# PWR_1_0.net
KiCad netlist of a schematic drawn in EAGLE
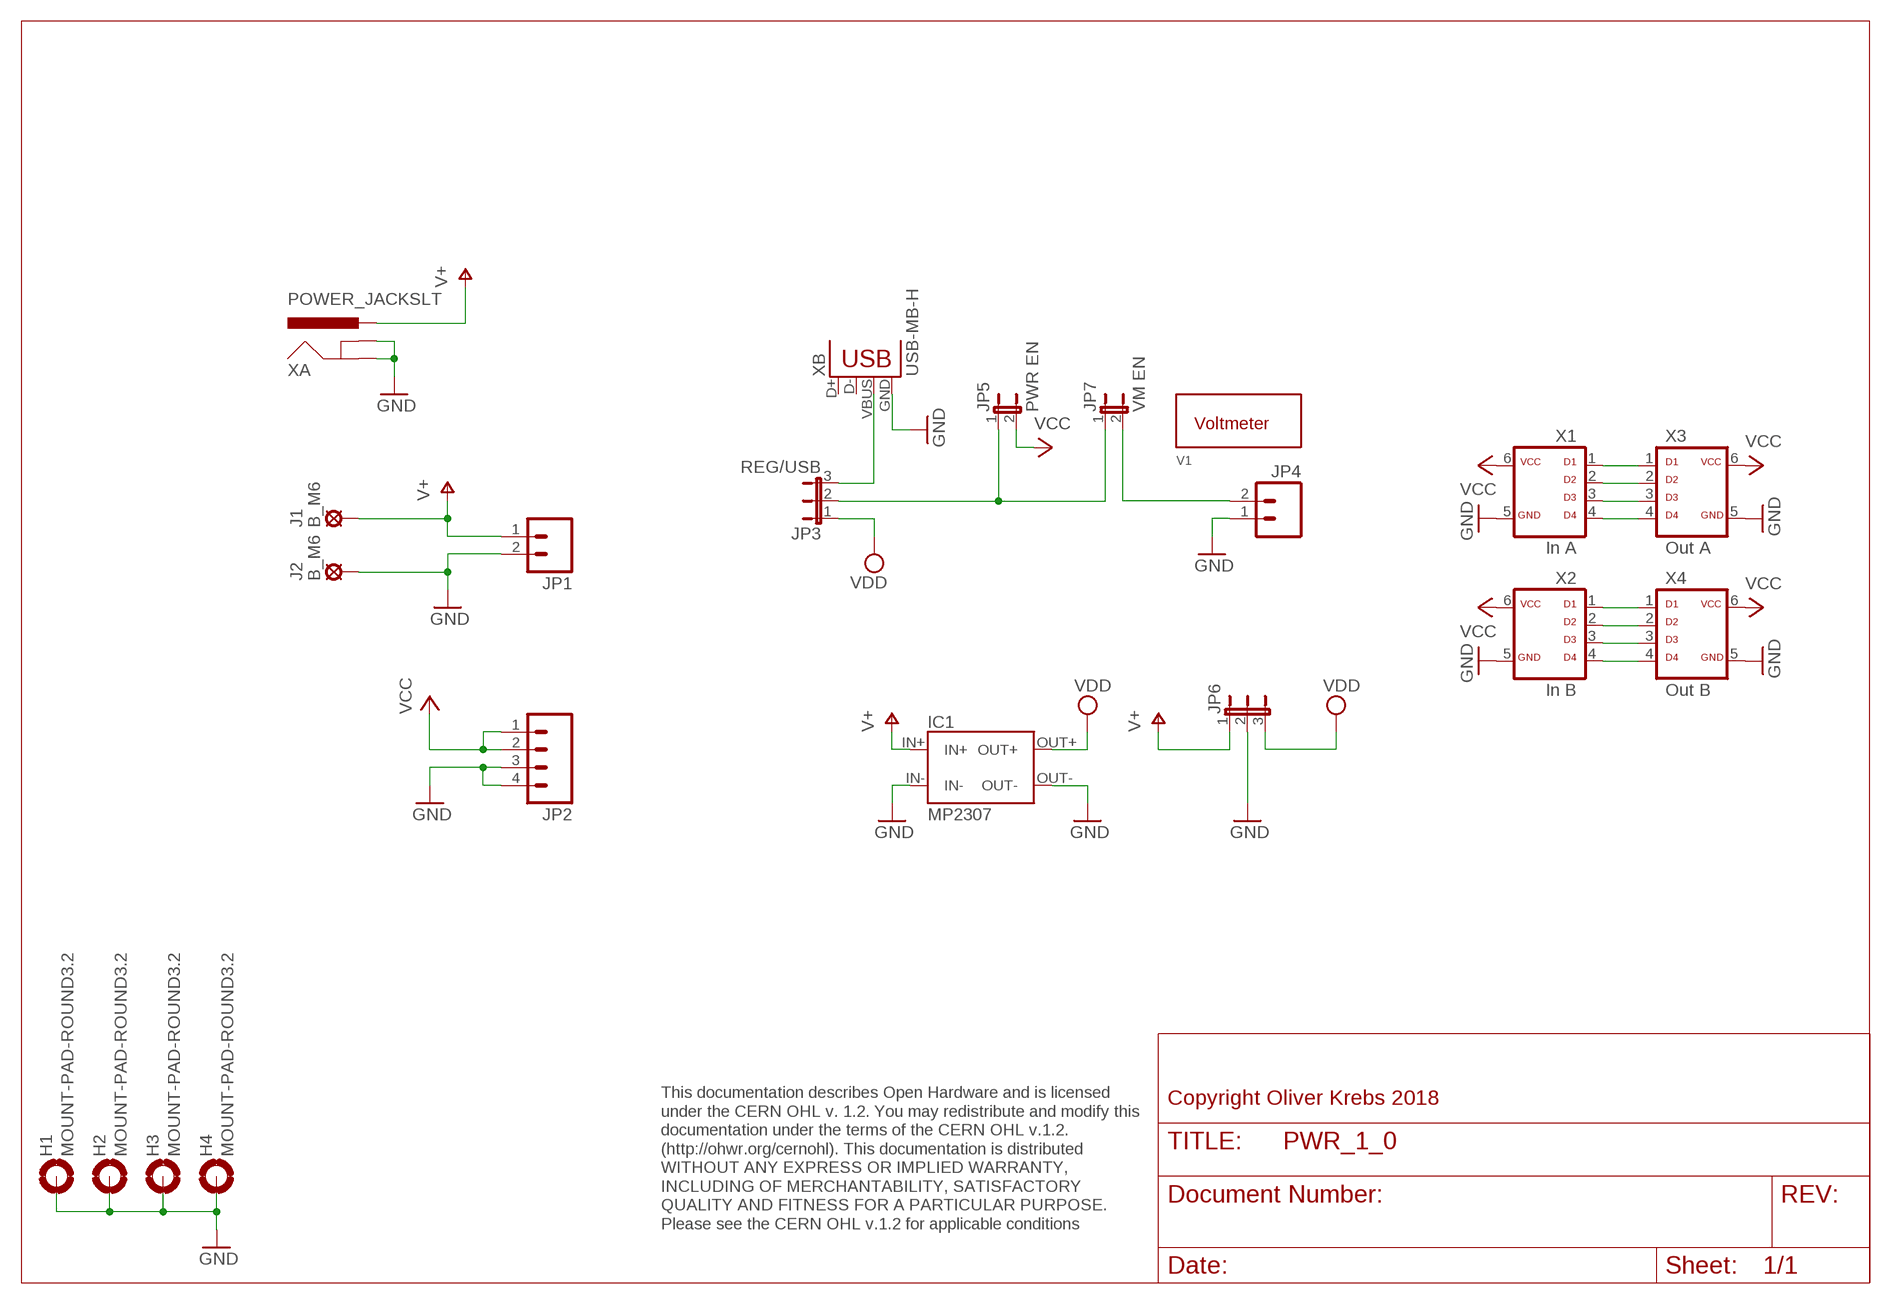
[diagram p0: schematic, sheet 1]

(export (version "E")
  (design (tool "Eeschema 10.0.6"))
  (components
    (comp (ref "H1")
      (value "MOUNT-PAD-ROUND3.2")
      (footprint "eagle-import:3,2-PAD")
      (libsource (lib "eagle-import") (part "MOUNT-PAD-ROUND3.2"))
    )
    (comp (ref "H2")
      (value "MOUNT-PAD-ROUND3.2")
      (footprint "eagle-import:3,2-PAD")
      (libsource (lib "eagle-import") (part "MOUNT-PAD-ROUND3.2"))
    )
    (comp (ref "H3")
      (value "MOUNT-PAD-ROUND3.2")
      (footprint "eagle-import:3,2-PAD")
      (libsource (lib "eagle-import") (part "MOUNT-PAD-ROUND3.2"))
    )
    (comp (ref "H4")
      (value "MOUNT-PAD-ROUND3.2")
      (footprint "eagle-import:3,2-PAD")
      (libsource (lib "eagle-import") (part "MOUNT-PAD-ROUND3.2"))
    )
    (comp (ref "IC1")
      (value "MP2307")
      (footprint "eagle-import:MP2307")
      (libsource (lib "eagle-import") (part "MP2307"))
    )
    (comp (ref "J1")
      (value "B_M6")
      (footprint "eagle-import:BANANA_M6")
      (libsource (lib "eagle-import") (part "B_M6"))
    )
    (comp (ref "J2")
      (value "B_M6")
      (footprint "eagle-import:BANANA_M6")
      (libsource (lib "eagle-import") (part "B_M6"))
    )
    (comp (ref "JP1")
      (value "M021.3MM-5.08")
      (footprint "eagle-import:1X02_BIG_5.08")
      (libsource (lib "eagle-import") (part "M021.3MM-5.08"))
    )
    (comp (ref "JP2")
      (value "M04PTH")
      (footprint "eagle-import:1X04")
      (libsource (lib "eagle-import") (part "M04PTH"))
    )
    (comp (ref "JP3")
      (value "REG/USB")
      (footprint "eagle-import:JP2-U")
      (libsource (lib "eagle-import") (part "JP2EJP2-U"))
    )
    (comp (ref "JP4")
      (value "M02PTH")
      (footprint "eagle-import:1X02")
      (libsource (lib "eagle-import") (part "M02PTH"))
    )
    (comp (ref "JP5")
      (value "PWR EN")
      (footprint "eagle-import:JP1")
      (libsource (lib "eagle-import") (part "JP1E"))
    )
    (comp (ref "JP6")
      (value "JP2EJP2-U")
      (footprint "eagle-import:JP2-U")
      (libsource (lib "eagle-import") (part "JP2EJP2-U"))
    )
    (comp (ref "JP7")
      (value "VM EN")
      (footprint "eagle-import:JP1")
      (libsource (lib "eagle-import") (part "JP1E"))
    )
    (comp (ref "V1")
      (value "VOLTMETER-28")
      (footprint "eagle-import:VOLTMETER-28")
      (libsource (lib "eagle-import") (part "VOLTMETER-28"))
    )
    (comp (ref "X1")
      (value "In A")
      (footprint "eagle-import:ML-6")
      (libsource (lib "eagle-import") (part "ML6D"))
    )
    (comp (ref "X2")
      (value "In B")
      (footprint "eagle-import:ML-6")
      (libsource (lib "eagle-import") (part "ML6D"))
    )
    (comp (ref "X3")
      (value "Out A")
      (footprint "eagle-import:ML-6")
      (libsource (lib "eagle-import") (part "ML6D"))
    )
    (comp (ref "X4")
      (value "Out B")
      (footprint "eagle-import:ML-6")
      (libsource (lib "eagle-import") (part "ML6D"))
    )
    (comp (ref "XA")
      (value "POWER_JACKSLT")
      (footprint "eagle-import:POWER_JACK_SLOT")
      (libsource (lib "eagle-import") (part "POWER_JACKSLT"))
    )
    (comp (ref "XB")
      (value "USB-MB-H")
      (footprint "eagle-import:USB-MB-H")
      (libsource (lib "eagle-import") (part "USB-MB-H"))
    )
  )
  (nets
    (net (code "1") (name "GND") (class "Default")
      (node (ref "H1") (pin "B3,2") (pinfunction "MOUNT_B3,2") (pintype "passive"))
      (node (ref "H2") (pin "B3,2") (pinfunction "MOUNT_B3,2") (pintype "passive"))
      (node (ref "H3") (pin "B3,2") (pinfunction "MOUNT_B3,2") (pintype "passive"))
      (node (ref "H4") (pin "B3,2") (pinfunction "MOUNT_B3,2") (pintype "passive"))
      (node (ref "IC1") (pin "IN-") (pinfunction "IN-_IN-") (pintype "bidirectional"))
      (node (ref "IC1") (pin "OUT-") (pinfunction "OUT-_OUT-") (pintype "bidirectional"))
      (node (ref "J2") (pin "1") (pinfunction "MP_1") (pintype "passive"))
      (node (ref "JP1") (pin "2") (pinfunction "2_2") (pintype "passive"))
      (node (ref "JP2") (pin "3") (pinfunction "3_3") (pintype "passive"))
      (node (ref "JP2") (pin "4") (pinfunction "4_4") (pintype "passive"))
      (node (ref "JP4") (pin "1") (pinfunction "1_1") (pintype "passive"))
      (node (ref "JP6") (pin "2") (pinfunction "2_2") (pintype "passive"))
      (node (ref "X1") (pin "5") (pinfunction "5_5") (pintype "passive"))
      (node (ref "X2") (pin "5") (pinfunction "5_5") (pintype "passive"))
      (node (ref "X3") (pin "5") (pinfunction "5_5") (pintype "passive"))
      (node (ref "X4") (pin "5") (pinfunction "5_5") (pintype "passive"))
      (node (ref "XA") (pin "GND@1") (pinfunction "GNDBREAK_GND@1") (pintype "bidirectional"))
      (node (ref "XA") (pin "GND@2") (pinfunction "GND_GND@2") (pintype "bidirectional"))
      (node (ref "XB") (pin "GND") (pinfunction "GND_GND") (pintype "bidirectional"))
    )
    (net (code "2") (name "Net-(JP3-Pad2)") (class "Default")
      (node (ref "JP3") (pin "2") (pinfunction "2_2") (pintype "passive"))
      (node (ref "JP5") (pin "1") (pinfunction "1_1") (pintype "passive"))
      (node (ref "JP7") (pin "1") (pinfunction "1_1") (pintype "passive"))
    )
    (net (code "3") (name "Net-(JP3-Pad3)") (class "Default")
      (node (ref "JP3") (pin "3") (pinfunction "3_3") (pintype "passive"))
      (node (ref "XB") (pin "VBUS") (pinfunction "VBUS_VBUS") (pintype "bidirectional"))
    )
    (net (code "4") (name "Net-(JP4-Pad2)") (class "Default")
      (node (ref "JP4") (pin "2") (pinfunction "2_2") (pintype "passive"))
      (node (ref "JP7") (pin "2") (pinfunction "2_2") (pintype "passive"))
    )
    (net (code "5") (name "Net-(X1-Pad1)") (class "Default")
      (node (ref "X1") (pin "1") (pinfunction "1_1") (pintype "passive"))
      (node (ref "X3") (pin "1") (pinfunction "1_1") (pintype "passive"))
    )
    (net (code "6") (name "Net-(X1-Pad2)") (class "Default")
      (node (ref "X1") (pin "2") (pinfunction "2_2") (pintype "passive"))
      (node (ref "X3") (pin "2") (pinfunction "2_2") (pintype "passive"))
    )
    (net (code "7") (name "Net-(X1-Pad3)") (class "Default")
      (node (ref "X1") (pin "3") (pinfunction "3_3") (pintype "passive"))
      (node (ref "X3") (pin "3") (pinfunction "3_3") (pintype "passive"))
    )
    (net (code "8") (name "Net-(X1-Pad4)") (class "Default")
      (node (ref "X1") (pin "4") (pinfunction "4_4") (pintype "passive"))
      (node (ref "X3") (pin "4") (pinfunction "4_4") (pintype "passive"))
    )
    (net (code "9") (name "Net-(X2-Pad1)") (class "Default")
      (node (ref "X2") (pin "1") (pinfunction "1_1") (pintype "passive"))
      (node (ref "X4") (pin "1") (pinfunction "1_1") (pintype "passive"))
    )
    (net (code "10") (name "Net-(X2-Pad2)") (class "Default")
      (node (ref "X2") (pin "2") (pinfunction "2_2") (pintype "passive"))
      (node (ref "X4") (pin "2") (pinfunction "2_2") (pintype "passive"))
    )
    (net (code "11") (name "Net-(X2-Pad3)") (class "Default")
      (node (ref "X2") (pin "3") (pinfunction "3_3") (pintype "passive"))
      (node (ref "X4") (pin "3") (pinfunction "3_3") (pintype "passive"))
    )
    (net (code "12") (name "Net-(X2-Pad4)") (class "Default")
      (node (ref "X2") (pin "4") (pinfunction "4_4") (pintype "passive"))
      (node (ref "X4") (pin "4") (pinfunction "4_4") (pintype "passive"))
    )
    (net (code "13") (name "V+") (class "Default")
      (node (ref "IC1") (pin "IN+") (pinfunction "IN+_IN+") (pintype "bidirectional"))
      (node (ref "J1") (pin "1") (pinfunction "MP_1") (pintype "passive"))
      (node (ref "JP1") (pin "1") (pinfunction "1_1") (pintype "passive"))
      (node (ref "JP6") (pin "1") (pinfunction "1_1") (pintype "passive"))
      (node (ref "XA") (pin "PWR") (pinfunction "PWR_PWR") (pintype "bidirectional"))
    )
    (net (code "14") (name "VCC") (class "Default")
      (node (ref "JP2") (pin "1") (pinfunction "1_1") (pintype "passive"))
      (node (ref "JP2") (pin "2") (pinfunction "2_2") (pintype "passive"))
      (node (ref "JP5") (pin "2") (pinfunction "2_2") (pintype "passive"))
      (node (ref "X1") (pin "6") (pinfunction "6_6") (pintype "passive"))
      (node (ref "X2") (pin "6") (pinfunction "6_6") (pintype "passive"))
      (node (ref "X3") (pin "6") (pinfunction "6_6") (pintype "passive"))
      (node (ref "X4") (pin "6") (pinfunction "6_6") (pintype "passive"))
    )
    (net (code "15") (name "VDD") (class "Default")
      (node (ref "IC1") (pin "OUT+") (pinfunction "OUT+_OUT+") (pintype "bidirectional"))
      (node (ref "JP3") (pin "1") (pinfunction "1_1") (pintype "passive"))
      (node (ref "JP6") (pin "3") (pinfunction "3_3") (pintype "passive"))
    )
    (net (code "16") (name "unconnected-(XB-PadD+)") (class "Default")
      (node (ref "XB") (pin "D+") (pinfunction "D+_D+") (pintype "bidirectional"))
    )
    (net (code "17") (name "unconnected-(XB-PadD-)") (class "Default")
      (node (ref "XB") (pin "D-") (pinfunction "D-_D-") (pintype "bidirectional"))
    )
  )
)
